# ISO_CAN.net
KiCad netlist of a schematic drawn in Altium Designer
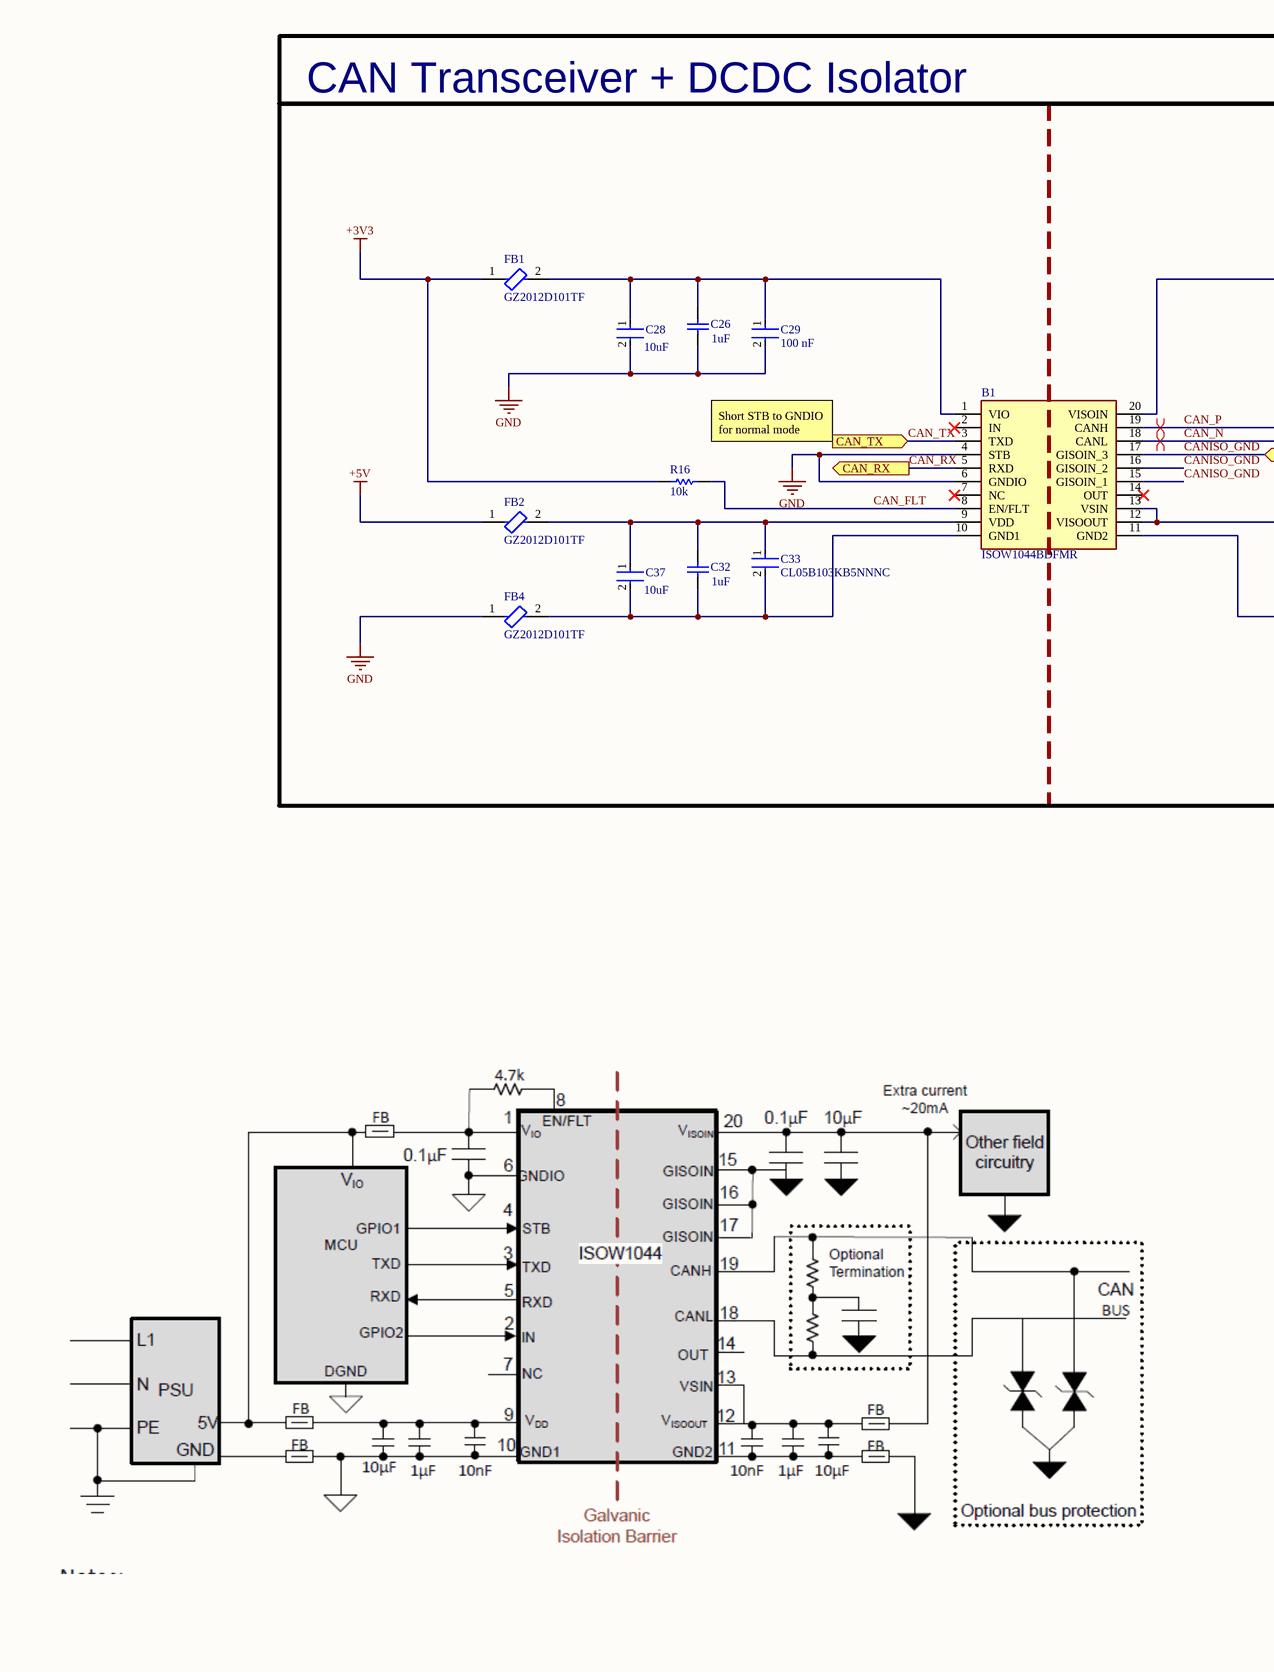
[diagram p0: ISO_CAN.SchDoc, top left]
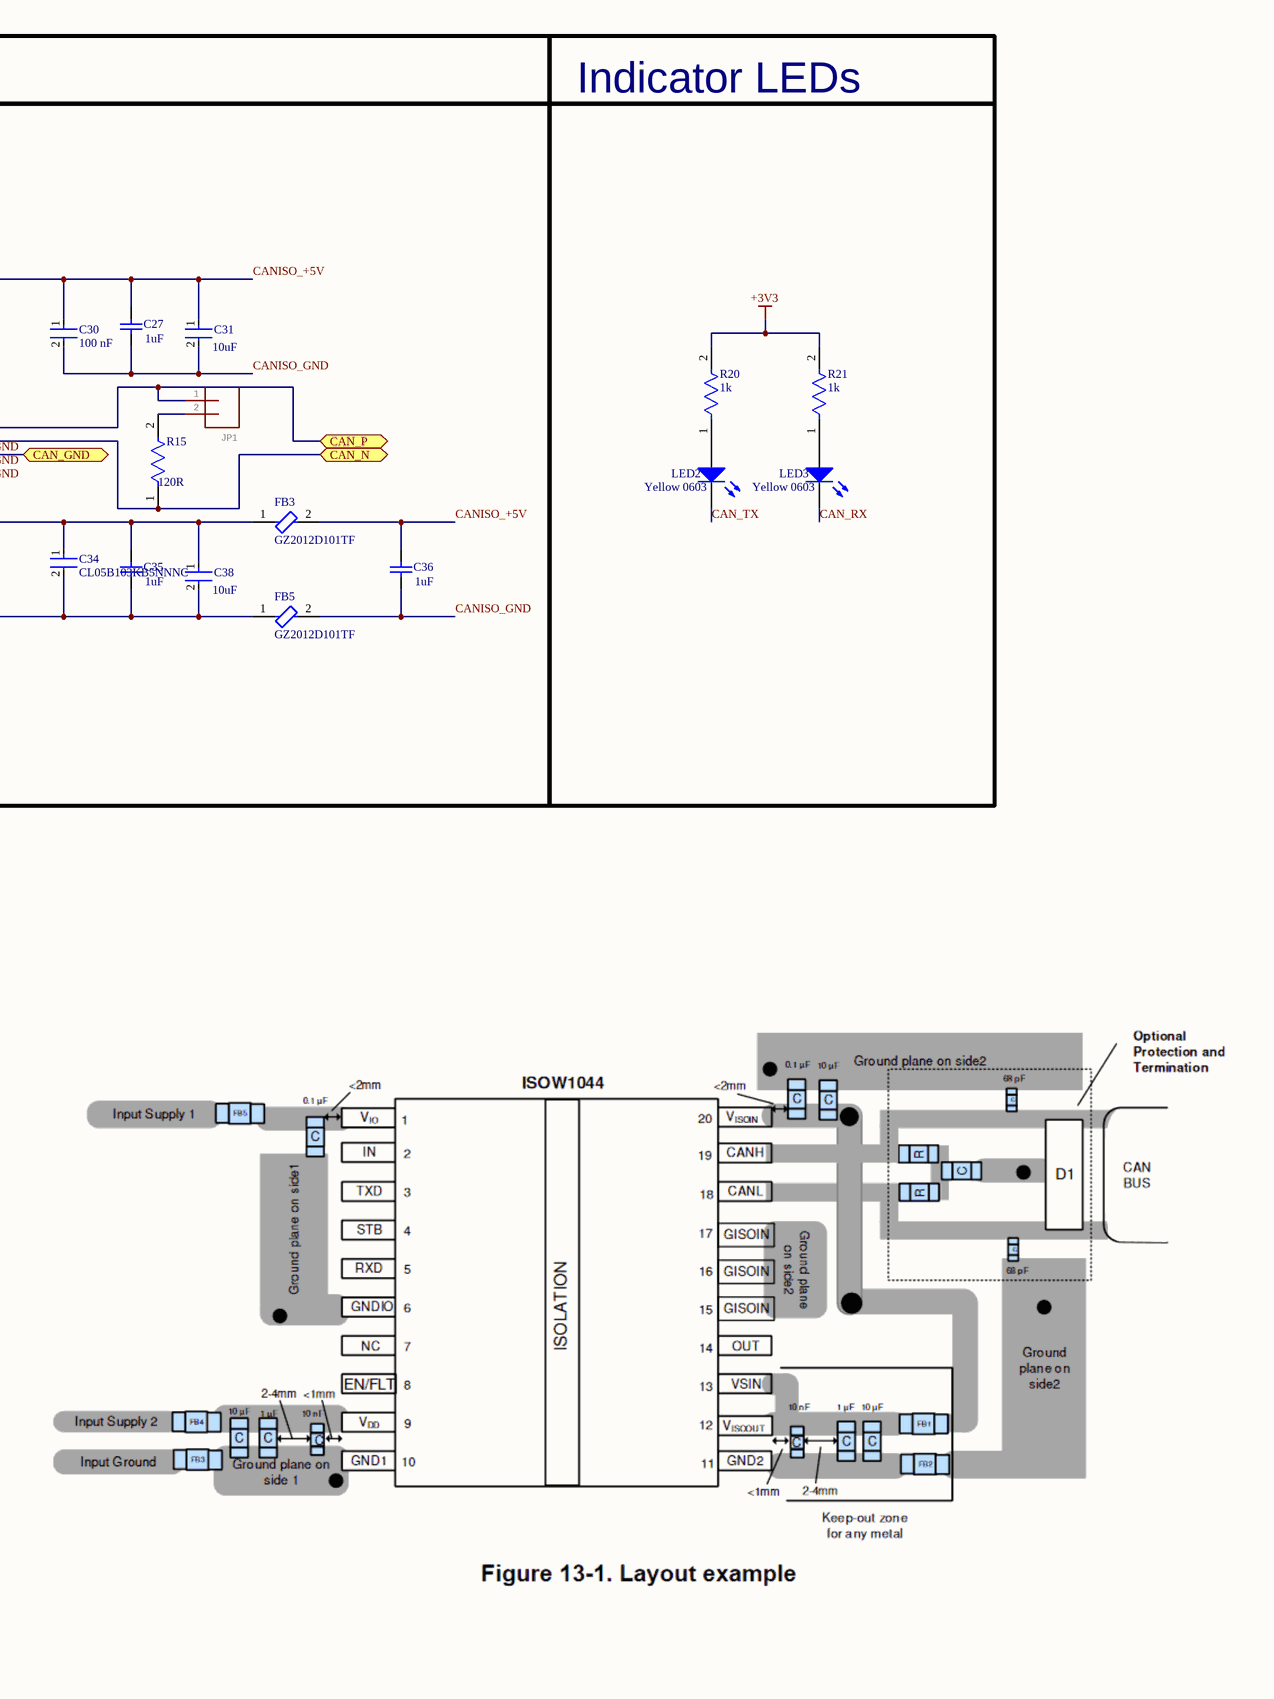
[diagram p1: ISO_CAN.SchDoc, top right]
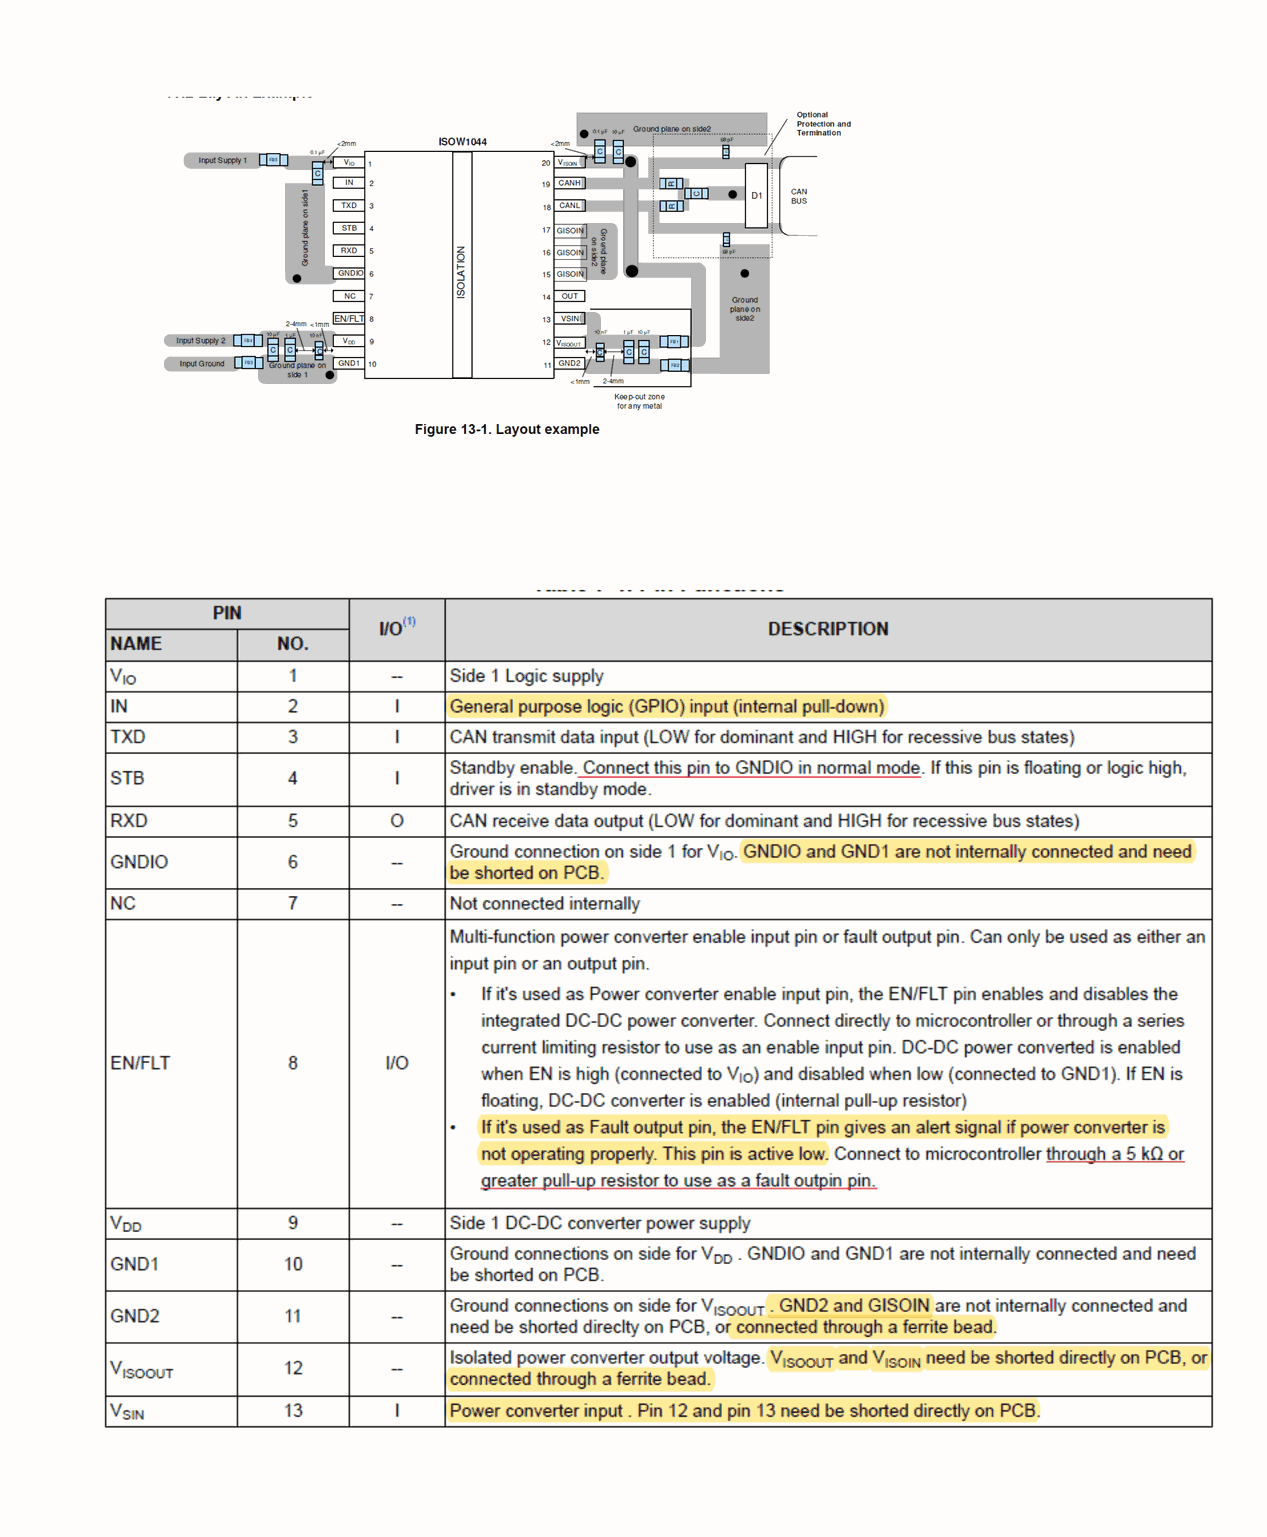
[diagram p2: ISO_CAN.SchDoc, bottom left]
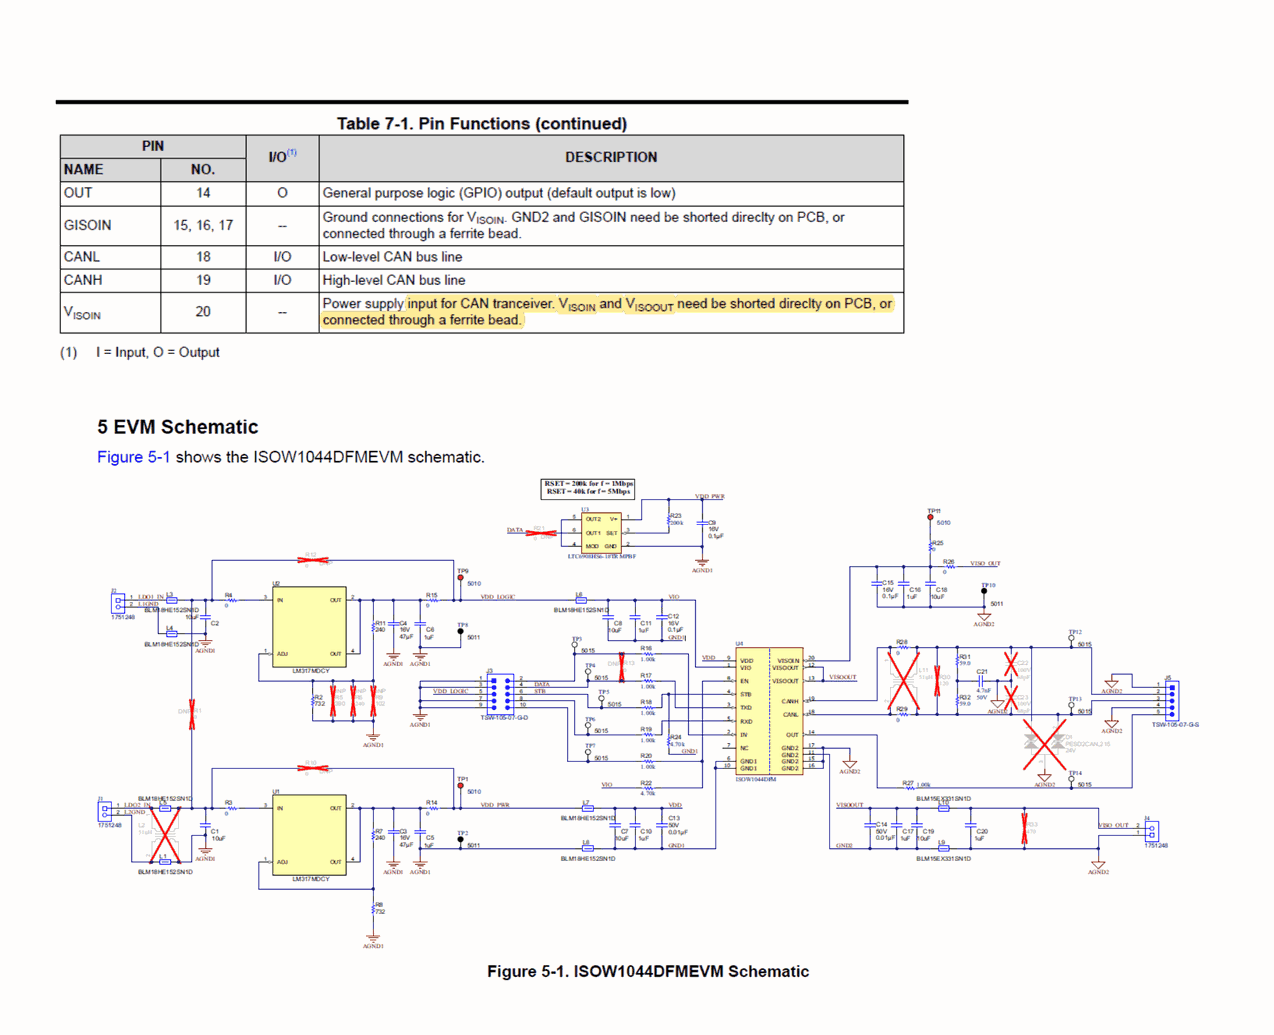
[diagram p3: ISO_CAN.SchDoc, bottom right]

(export (version "E")
  (design (tool "Eeschema 10.0.6"))
  (components
    (comp (ref "B1")
      (value "ISOW1044BDFMR")
      (footprint "SOIC127P1030X355-20N")
      (description "Texas Instruments")
      (fields (field (name "MOUSER PART NUMBER") "595-ISOW1044BDFMR"))
      (libsource (lib "BumbleBee Autonomous Systems - NUS") (part "ISOW1044BDFMR"))
    )
    (comp (ref "C26")
      (value "1uF")
      (footprint "CAPC1608X95N")
      (fields (field (name "Comment") "1uF 0603"))
      (libsource (lib "BumbleBee Autonomous Systems - NUS") (part "CAP"))
    )
    (comp (ref "C27")
      (value "1uF")
      (footprint "CAPC1608X95N")
      (fields (field (name "Comment") "1uF 0603"))
      (libsource (lib "BumbleBee Autonomous Systems - NUS") (part "CAP"))
    )
    (comp (ref "C28")
      (value "GRM21BR61H106KE43L")
      (footprint "FP-GRM21B-0_2-e0_2_0_7-IPC_A")
      (description "Chip Multilayer Ceramic Capacitors for General Purpose, 0805, 10uF, X5R, 15%, 10%, 50V")
      (fields (field (name "TOLERANCE") "10%") (field (name "CAPACITANCE") "10uF"))
      (libsource (lib "Altium Content Vault") (part "b4654b650e69147ec39a6b967a45e02"))
    )
    (comp (ref "C29")
      (value "CC0603KRX7R9BB104")
      (footprint "FP-CC0603-DA-MFG")
      (description "CAP CER 0.1UF 50V X7R 0603")
      (fields
        (field (name "MANUFACTURER") "YAGEO")
        (field (name "VOLTAGE") "50 V")
        (field (name "CAPACITANCE") "100 nF")
      )
      (libsource (lib "Altium Content Vault") (part "11868f565c42a9108669ba33697ecf6"))
    )
    (comp (ref "C30")
      (value "CC0603KRX7R9BB104")
      (footprint "FP-CC0603-DA-MFG")
      (description "CAP CER 0.1UF 50V X7R 0603")
      (fields
        (field (name "MANUFACTURER") "YAGEO")
        (field (name "VOLTAGE") "50 V")
        (field (name "CAPACITANCE") "100 nF")
      )
      (libsource (lib "Altium Content Vault") (part "11868f565c42a9108669ba33697ecf6"))
    )
    (comp (ref "C31")
      (value "GRM21BR61H106KE43L")
      (footprint "FP-GRM21B-0_2-e0_2_0_7-IPC_A")
      (description "Chip Multilayer Ceramic Capacitors for General Purpose, 0805, 10uF, X5R, 15%, 10%, 50V")
      (fields (field (name "TOLERANCE") "10%") (field (name "CAPACITANCE") "10uF"))
      (libsource (lib "Altium Content Vault") (part "b4654b650e69147ec39a6b967a45e02"))
    )
    (comp (ref "C32")
      (value "1uF")
      (footprint "CAPC1608X95N")
      (fields (field (name "Comment") "1uF 0603"))
      (libsource (lib "BumbleBee Autonomous Systems - NUS") (part "CAP"))
    )
    (comp (ref "C33")
      (value "CL05B103KB5NNNC")
      (footprint "FP-CL165-IPC_C")
      (description "Cap Ceramic 10nF 50V X7R ±10% SMD 0402 +125°C Paper T/R")
      (fields (field (name "VOLTAGE") "50V") (field (name "TOLERANCE") "10%"))
      (libsource (lib "Altium Content Vault") (part "b4654b650e69147ec39a6b967a45e02"))
    )
    (comp (ref "C34")
      (value "CL05B103KB5NNNC")
      (footprint "FP-CL165-IPC_C")
      (description "Cap Ceramic 10nF 50V X7R ±10% SMD 0402 +125°C Paper T/R")
      (fields (field (name "VOLTAGE") "50V") (field (name "TOLERANCE") "10%"))
      (libsource (lib "Altium Content Vault") (part "b4654b650e69147ec39a6b967a45e02"))
    )
    (comp (ref "C35")
      (value "1uF")
      (footprint "CAPC1608X95N")
      (fields (field (name "Comment") "1uF 0603"))
      (libsource (lib "BumbleBee Autonomous Systems - NUS") (part "CAP"))
    )
    (comp (ref "C36")
      (value "1uF")
      (footprint "CAPC1608X95N")
      (fields (field (name "Comment") "1uF 0603"))
      (libsource (lib "BumbleBee Autonomous Systems - NUS") (part "CAP"))
    )
    (comp (ref "C37")
      (value "GRM21BR61H106KE43L")
      (footprint "FP-GRM21B-0_2-e0_2_0_7-IPC_A")
      (description "Chip Multilayer Ceramic Capacitors for General Purpose, 0805, 10uF, X5R, 15%, 10%, 50V")
      (fields (field (name "TOLERANCE") "10%") (field (name "CAPACITANCE") "10uF"))
      (libsource (lib "Altium Content Vault") (part "b4654b650e69147ec39a6b967a45e02"))
    )
    (comp (ref "C38")
      (value "GRM21BR61H106KE43L")
      (footprint "FP-GRM21B-0_2-e0_2_0_7-IPC_A")
      (description "Chip Multilayer Ceramic Capacitors for General Purpose, 0805, 10uF, X5R, 15%, 10%, 50V")
      (fields (field (name "TOLERANCE") "10%") (field (name "CAPACITANCE") "10uF"))
      (libsource (lib "Altium Content Vault") (part "b4654b650e69147ec39a6b967a45e02"))
    )
    (comp (ref "FB1")
      (value "GZ2012D101TF")
      (footprint "FP-BLM21-0_2-t0_85-e0_5-IPC_A")
      (description "±25% 100Ω@100MHz 0805 Ferrite Beads ROHS")
      (libsource (lib "Altium Content Vault") (part "5f30dd21d616792df468990f7003faa"))
    )
    (comp (ref "FB2")
      (value "GZ2012D101TF")
      (footprint "FP-BLM21-0_2-t0_85-e0_5-IPC_A")
      (description "±25% 100Ω@100MHz 0805 Ferrite Beads ROHS")
      (libsource (lib "Altium Content Vault") (part "5f30dd21d616792df468990f7003faa"))
    )
    (comp (ref "FB3")
      (value "GZ2012D101TF")
      (footprint "FP-BLM21-0_2-t0_85-e0_5-IPC_A")
      (description "±25% 100Ω@100MHz 0805 Ferrite Beads ROHS")
      (libsource (lib "Altium Content Vault") (part "5f30dd21d616792df468990f7003faa"))
    )
    (comp (ref "FB4")
      (value "GZ2012D101TF")
      (footprint "FP-BLM21-0_2-t0_85-e0_5-IPC_A")
      (description "±25% 100Ω@100MHz 0805 Ferrite Beads ROHS")
      (libsource (lib "Altium Content Vault") (part "5f30dd21d616792df468990f7003faa"))
    )
    (comp (ref "FB5")
      (value "GZ2012D101TF")
      (footprint "FP-BLM21-0_2-t0_85-e0_5-IPC_A")
      (description "±25% 100Ω@100MHz 0805 Ferrite Beads ROHS")
      (libsource (lib "Altium Content Vault") (part "5f30dd21d616792df468990f7003faa"))
    )
    (comp (ref "JP1")
      (value "Multi connection point. Often used as Generic Header-pin footprint for 0.1 inch spaced/style header connections    On any of the 0.1 inch spaced packages, you can populate with these:  Break Away Headers - Straight (PRT-00116)   Break Away Male Headers - Right Angle (PRT-00553)   Female Headers (PRT-00115)   Break Away Headers - Machine Pin (PRT-00117)   Break Away Female Headers - Swiss Machine Pin (PRT-00743)        For SCREWTERMINALS and SPRING TERMINALS visit here:  Screw Terimnals on SparkFun.com (5mm/3.5mm/2.54mm spacing)       This device is also useful as a general connection point to wire up your design to another part of your project. Our various solder wires solder well into these plated through hole pads.  Hook-Up Wire - Assortment (Stranded, 22 AWG) (PRT-11375)   Hook-Up Wire - Assortment (Solid Core, 22 AWG) (PRT-11367)   View the entire wire category on our website here          Special notes: Molex polarized connector foot print use with: PRT-08233 with associated crimp pins and housings.  2.54_SCREWTERM for use with  PRT-10571.  3.5mm Screw Terminal footprints for  PRT-08084  5mm Screw Terminal footprints for use with PRT-08432")
      (footprint "1X02_LOCK")
      (libsource (lib "SparkFun-Connectors.Library") (part "CONN_02LOCK"))
    )
    (comp (ref "LED2")
      (value "Yellow 0603")
      (footprint "0603_A")
      (description "Led, Yellow, 590 Nm, 2 V, 30 Ma, 120 Mcd Rohs Compliant: Yes")
      (fields (field (name "MANUFACTURER PART NO.") "150060YS75000"))
      (libsource (lib "BumbleBee Autonomous Systems - NUS") (part "WE-LED_K1A2-2"))
    )
    (comp (ref "LED3")
      (value "Yellow 0603")
      (footprint "0603_A")
      (description "Led, Yellow, 590 Nm, 2 V, 30 Ma, 120 Mcd Rohs Compliant: Yes")
      (fields (field (name "MANUFACTURER PART NO.") "150060YS75000"))
      (libsource (lib "BumbleBee Autonomous Systems - NUS") (part "WE-LED_K1A2-2"))
    )
    (comp (ref "R15")
      (value "0603WAF1200T5E")
      (footprint "FP-CRCW0603-e3-MFG")
      (description "100mW Thick Film Resistors 75V ±100ppm/℃ ±1% 120Ω 0603 Chip Resistor - Surface Mount ROHS")
      (fields (field (name "TOLERANCE") "1%") (field (name "RESISTANCE") "120R"))
      (libsource (lib "Altium Content Vault") (part "1029c3af85768c4190bb7ad29bc67b5"))
    )
    (comp (ref "R16")
      (value "0603WAF1002T5E")
      (footprint "RESC1609X50X30NL8T20")
      (description "100mW Thick Film Resistors 75V ±100ppm/℃ ±1% 10kΩ 0603 Chip Resistor - Surface Mount ROHS")
      (fields (field (name "RESISTANCE") "10k"))
      (libsource (lib "Altium Content Vault") (part "RES-2"))
    )
    (comp (ref "R20")
      (value "1k")
      (footprint "FP-RC0603-0_55-IPC_C")
      (description "RC0603FR-071KL. RES 1K OHM 1% 1/10W 0603")
      (fields (field (name "TOLERANCE") "1%"))
      (libsource (lib "Altium Content Vault") (part "1029c3af85768c4190bb7ad29bc67b5"))
    )
    (comp (ref "R21")
      (value "1k")
      (footprint "FP-RC0603-0_55-IPC_C")
      (description "RC0603FR-071KL. RES 1K OHM 1% 1/10W 0603")
      (fields (field (name "TOLERANCE") "1%"))
      (libsource (lib "Altium Content Vault") (part "1029c3af85768c4190bb7ad29bc67b5"))
    )
  )
  (nets
    (net (code "1") (name "+3V3") (class "Default")
      (node (ref "FB1") (pin "1") (pinfunction "1_1") (pintype "passive"))
      (node (ref "R16") (pin "1") (pinfunction "1_1") (pintype "passive"))
      (node (ref "R20") (pin "2") (pinfunction "2_2") (pintype "passive"))
      (node (ref "R21") (pin "2") (pinfunction "2_2") (pintype "passive"))
    )
    (net (code "2") (name "+5V") (class "Default")
      (node (ref "FB2") (pin "1") (pinfunction "1_1") (pintype "passive"))
    )
    (net (code "3") (name "/CANISO_+5V") (class "Default")
      (node (ref "B1") (pin "20") (pinfunction "VISOIN_20") (pintype "passive"))
      (node (ref "C27") (pin "2") (pinfunction "2_2") (pintype "passive"))
      (node (ref "C30") (pin "1") (pinfunction "1_1") (pintype "passive"))
      (node (ref "C31") (pin "1") (pinfunction "1_1") (pintype "passive"))
      (node (ref "C36") (pin "2") (pinfunction "2_2") (pintype "passive"))
      (node (ref "FB3") (pin "2") (pinfunction "2_2") (pintype "passive"))
    )
    (net (code "4") (name "/CANISO_GND") (class "Default")
      (node (ref "B1") (pin "15") (pinfunction "GISOIN_1_15") (pintype "passive"))
      (node (ref "B1") (pin "16") (pinfunction "GISOIN_2_16") (pintype "passive"))
      (node (ref "B1") (pin "17") (pinfunction "GISOIN_3_17") (pintype "passive"))
      (node (ref "C27") (pin "1") (pinfunction "1_1") (pintype "passive"))
      (node (ref "C30") (pin "2") (pinfunction "2_2") (pintype "passive"))
      (node (ref "C31") (pin "2") (pinfunction "2_2") (pintype "passive"))
      (node (ref "C36") (pin "1") (pinfunction "1_1") (pintype "passive"))
      (node (ref "FB5") (pin "2") (pinfunction "2_2") (pintype "passive"))
    )
    (net (code "5") (name "/CAN_FLT") (class "Default")
      (node (ref "B1") (pin "8") (pinfunction "EN/FLT_8") (pintype "passive"))
      (node (ref "R16") (pin "2") (pinfunction "2_2") (pintype "passive"))
    )
    (net (code "6") (name "/CAN_N") (class "Default")
      (node (ref "B1") (pin "18") (pinfunction "CANL_18") (pintype "passive"))
      (node (ref "R15") (pin "1") (pinfunction "1_1") (pintype "passive"))
    )
    (net (code "7") (name "/CAN_P") (class "Default")
      (node (ref "B1") (pin "19") (pinfunction "CANH_19") (pintype "passive"))
      (node (ref "JP1") (pin "1") (pinfunction "1_1") (pintype "passive"))
    )
    (net (code "8") (name "/CAN_RX") (class "Default")
      (node (ref "B1") (pin "5") (pinfunction "RXD_5") (pintype "passive"))
      (node (ref "LED3") (pin "1") (pinfunction "K_1") (pintype "passive"))
    )
    (net (code "9") (name "/CAN_TX") (class "Default")
      (node (ref "B1") (pin "3") (pinfunction "TXD_3") (pintype "passive"))
      (node (ref "LED2") (pin "1") (pinfunction "K_1") (pintype "passive"))
    )
    (net (code "10") (name "GND") (class "Default")
      (node (ref "B1") (pin "4") (pinfunction "STB_4") (pintype "passive"))
      (node (ref "B1") (pin "6") (pinfunction "GNDIO_6") (pintype "passive"))
      (node (ref "C26") (pin "1") (pinfunction "1_1") (pintype "passive"))
      (node (ref "C28") (pin "2") (pinfunction "2_2") (pintype "passive"))
      (node (ref "C29") (pin "2") (pinfunction "2_2") (pintype "passive"))
      (node (ref "FB4") (pin "1") (pinfunction "1_1") (pintype "passive"))
    )
    (net (code "11") (name "Net-(B1-GND1)") (class "Default")
      (node (ref "B1") (pin "10") (pinfunction "GND1_10") (pintype "passive"))
      (node (ref "C32") (pin "1") (pinfunction "1_1") (pintype "passive"))
      (node (ref "C33") (pin "2") (pinfunction "2_2") (pintype "passive"))
      (node (ref "C37") (pin "2") (pinfunction "2_2") (pintype "passive"))
      (node (ref "FB4") (pin "2") (pinfunction "2_2") (pintype "passive"))
    )
    (net (code "12") (name "Net-(B1-GND2)") (class "Default")
      (node (ref "B1") (pin "11") (pinfunction "GND2_11") (pintype "passive"))
      (node (ref "C34") (pin "2") (pinfunction "2_2") (pintype "passive"))
      (node (ref "C35") (pin "1") (pinfunction "1_1") (pintype "passive"))
      (node (ref "C38") (pin "2") (pinfunction "2_2") (pintype "passive"))
      (node (ref "FB5") (pin "1") (pinfunction "1_1") (pintype "passive"))
    )
    (net (code "13") (name "Net-(B1-VDD)") (class "Default")
      (node (ref "B1") (pin "9") (pinfunction "VDD_9") (pintype "passive"))
      (node (ref "C32") (pin "2") (pinfunction "2_2") (pintype "passive"))
      (node (ref "C33") (pin "1") (pinfunction "1_1") (pintype "passive"))
      (node (ref "C37") (pin "1") (pinfunction "1_1") (pintype "passive"))
      (node (ref "FB2") (pin "2") (pinfunction "2_2") (pintype "passive"))
    )
    (net (code "14") (name "Net-(B1-VIO)") (class "Default")
      (node (ref "B1") (pin "1") (pinfunction "VIO_1") (pintype "passive"))
      (node (ref "C26") (pin "2") (pinfunction "2_2") (pintype "passive"))
      (node (ref "C28") (pin "1") (pinfunction "1_1") (pintype "passive"))
      (node (ref "C29") (pin "1") (pinfunction "1_1") (pintype "passive"))
      (node (ref "FB1") (pin "2") (pinfunction "2_2") (pintype "passive"))
    )
    (net (code "15") (name "Net-(B1-VISOOUT)") (class "Default")
      (node (ref "B1") (pin "12") (pinfunction "VISOOUT_12") (pintype "passive"))
      (node (ref "B1") (pin "13") (pinfunction "VSIN_13") (pintype "passive"))
      (node (ref "C34") (pin "1") (pinfunction "1_1") (pintype "passive"))
      (node (ref "C35") (pin "2") (pinfunction "2_2") (pintype "passive"))
      (node (ref "C38") (pin "1") (pinfunction "1_1") (pintype "passive"))
      (node (ref "FB3") (pin "1") (pinfunction "1_1") (pintype "passive"))
    )
    (net (code "16") (name "Net-(JP1-Pad2)") (class "Default")
      (node (ref "JP1") (pin "2") (pinfunction "2_2") (pintype "passive"))
      (node (ref "R15") (pin "2") (pinfunction "2_2") (pintype "passive"))
    )
    (net (code "17") (name "Net-(LED2-A)") (class "Default")
      (node (ref "LED2") (pin "2") (pinfunction "A_2") (pintype "passive"))
      (node (ref "R20") (pin "1") (pinfunction "1_1") (pintype "passive"))
    )
    (net (code "18") (name "Net-(LED3-A)") (class "Default")
      (node (ref "LED3") (pin "2") (pinfunction "A_2") (pintype "passive"))
      (node (ref "R21") (pin "1") (pinfunction "1_1") (pintype "passive"))
    )
    (net (code "19") (name "unconnected-(B1-IN-Pad2)") (class "Default")
      (node (ref "B1") (pin "2") (pinfunction "IN_2") (pintype "passive+no_connect"))
    )
    (net (code "20") (name "unconnected-(B1-NC-Pad7)") (class "Default")
      (node (ref "B1") (pin "7") (pinfunction "NC_7") (pintype "passive+no_connect"))
    )
    (net (code "21") (name "unconnected-(B1-OUT-Pad14)") (class "Default")
      (node (ref "B1") (pin "14") (pinfunction "OUT_14") (pintype "passive+no_connect"))
    )
  )
)
